# v1.net
KiCad netlist of a schematic drawn in EAGLE
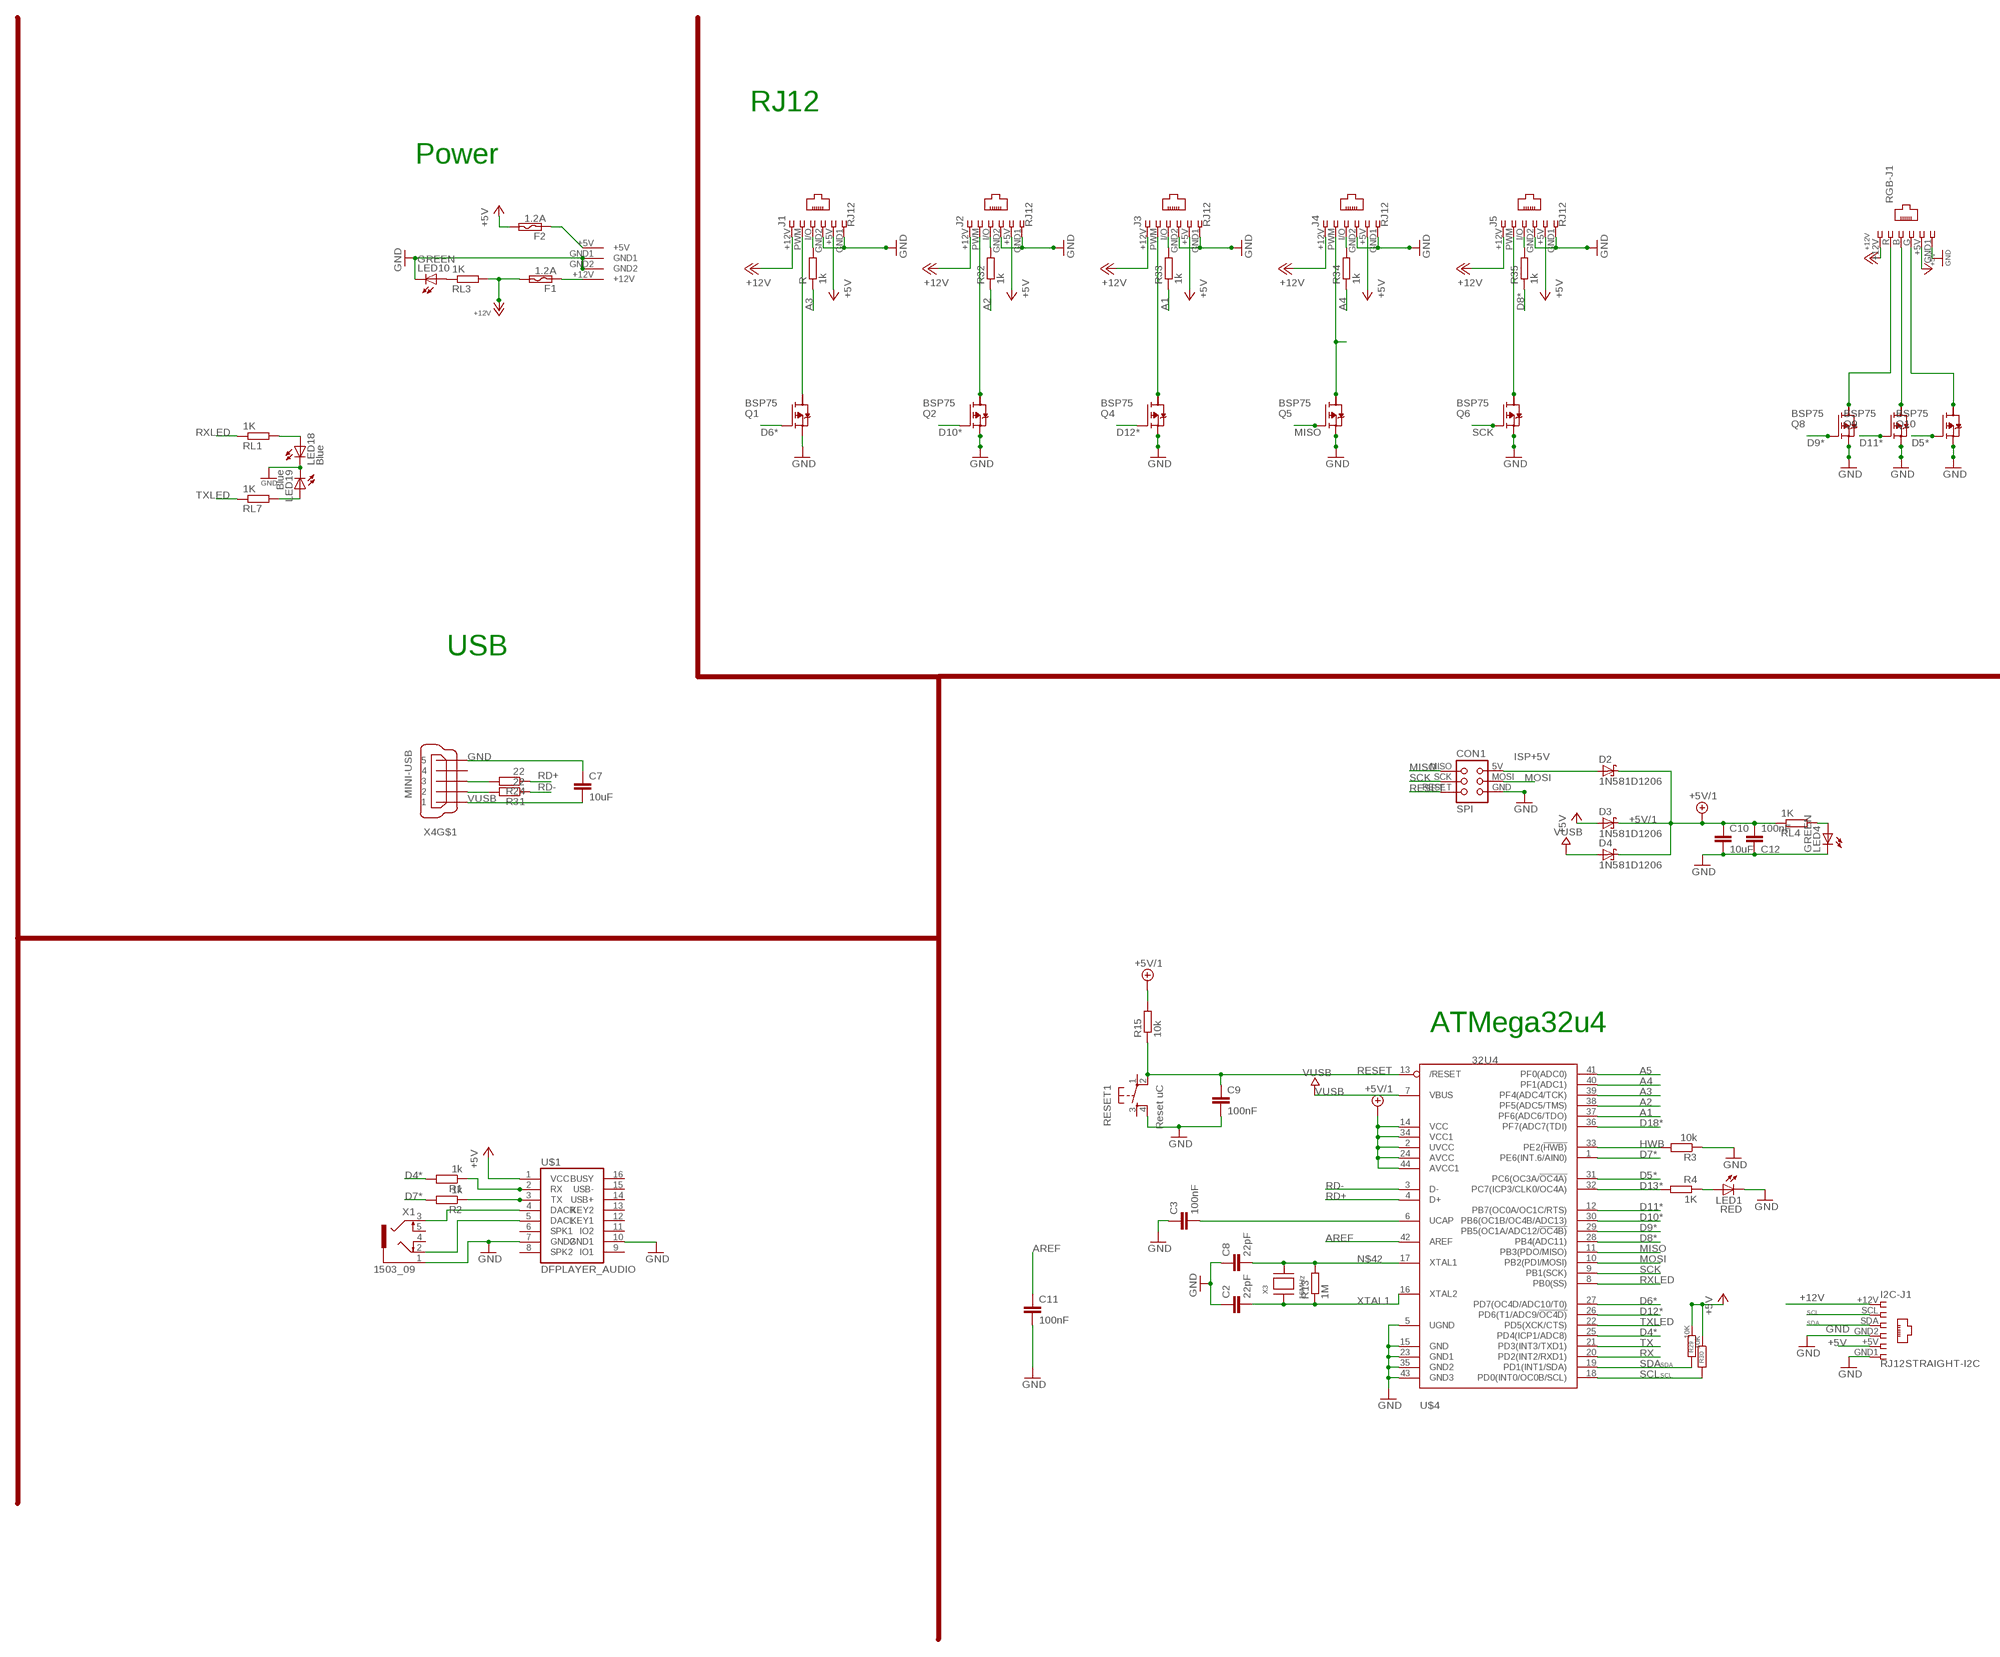
[diagram p0: schematic, sheet 1, part 1 of 2]
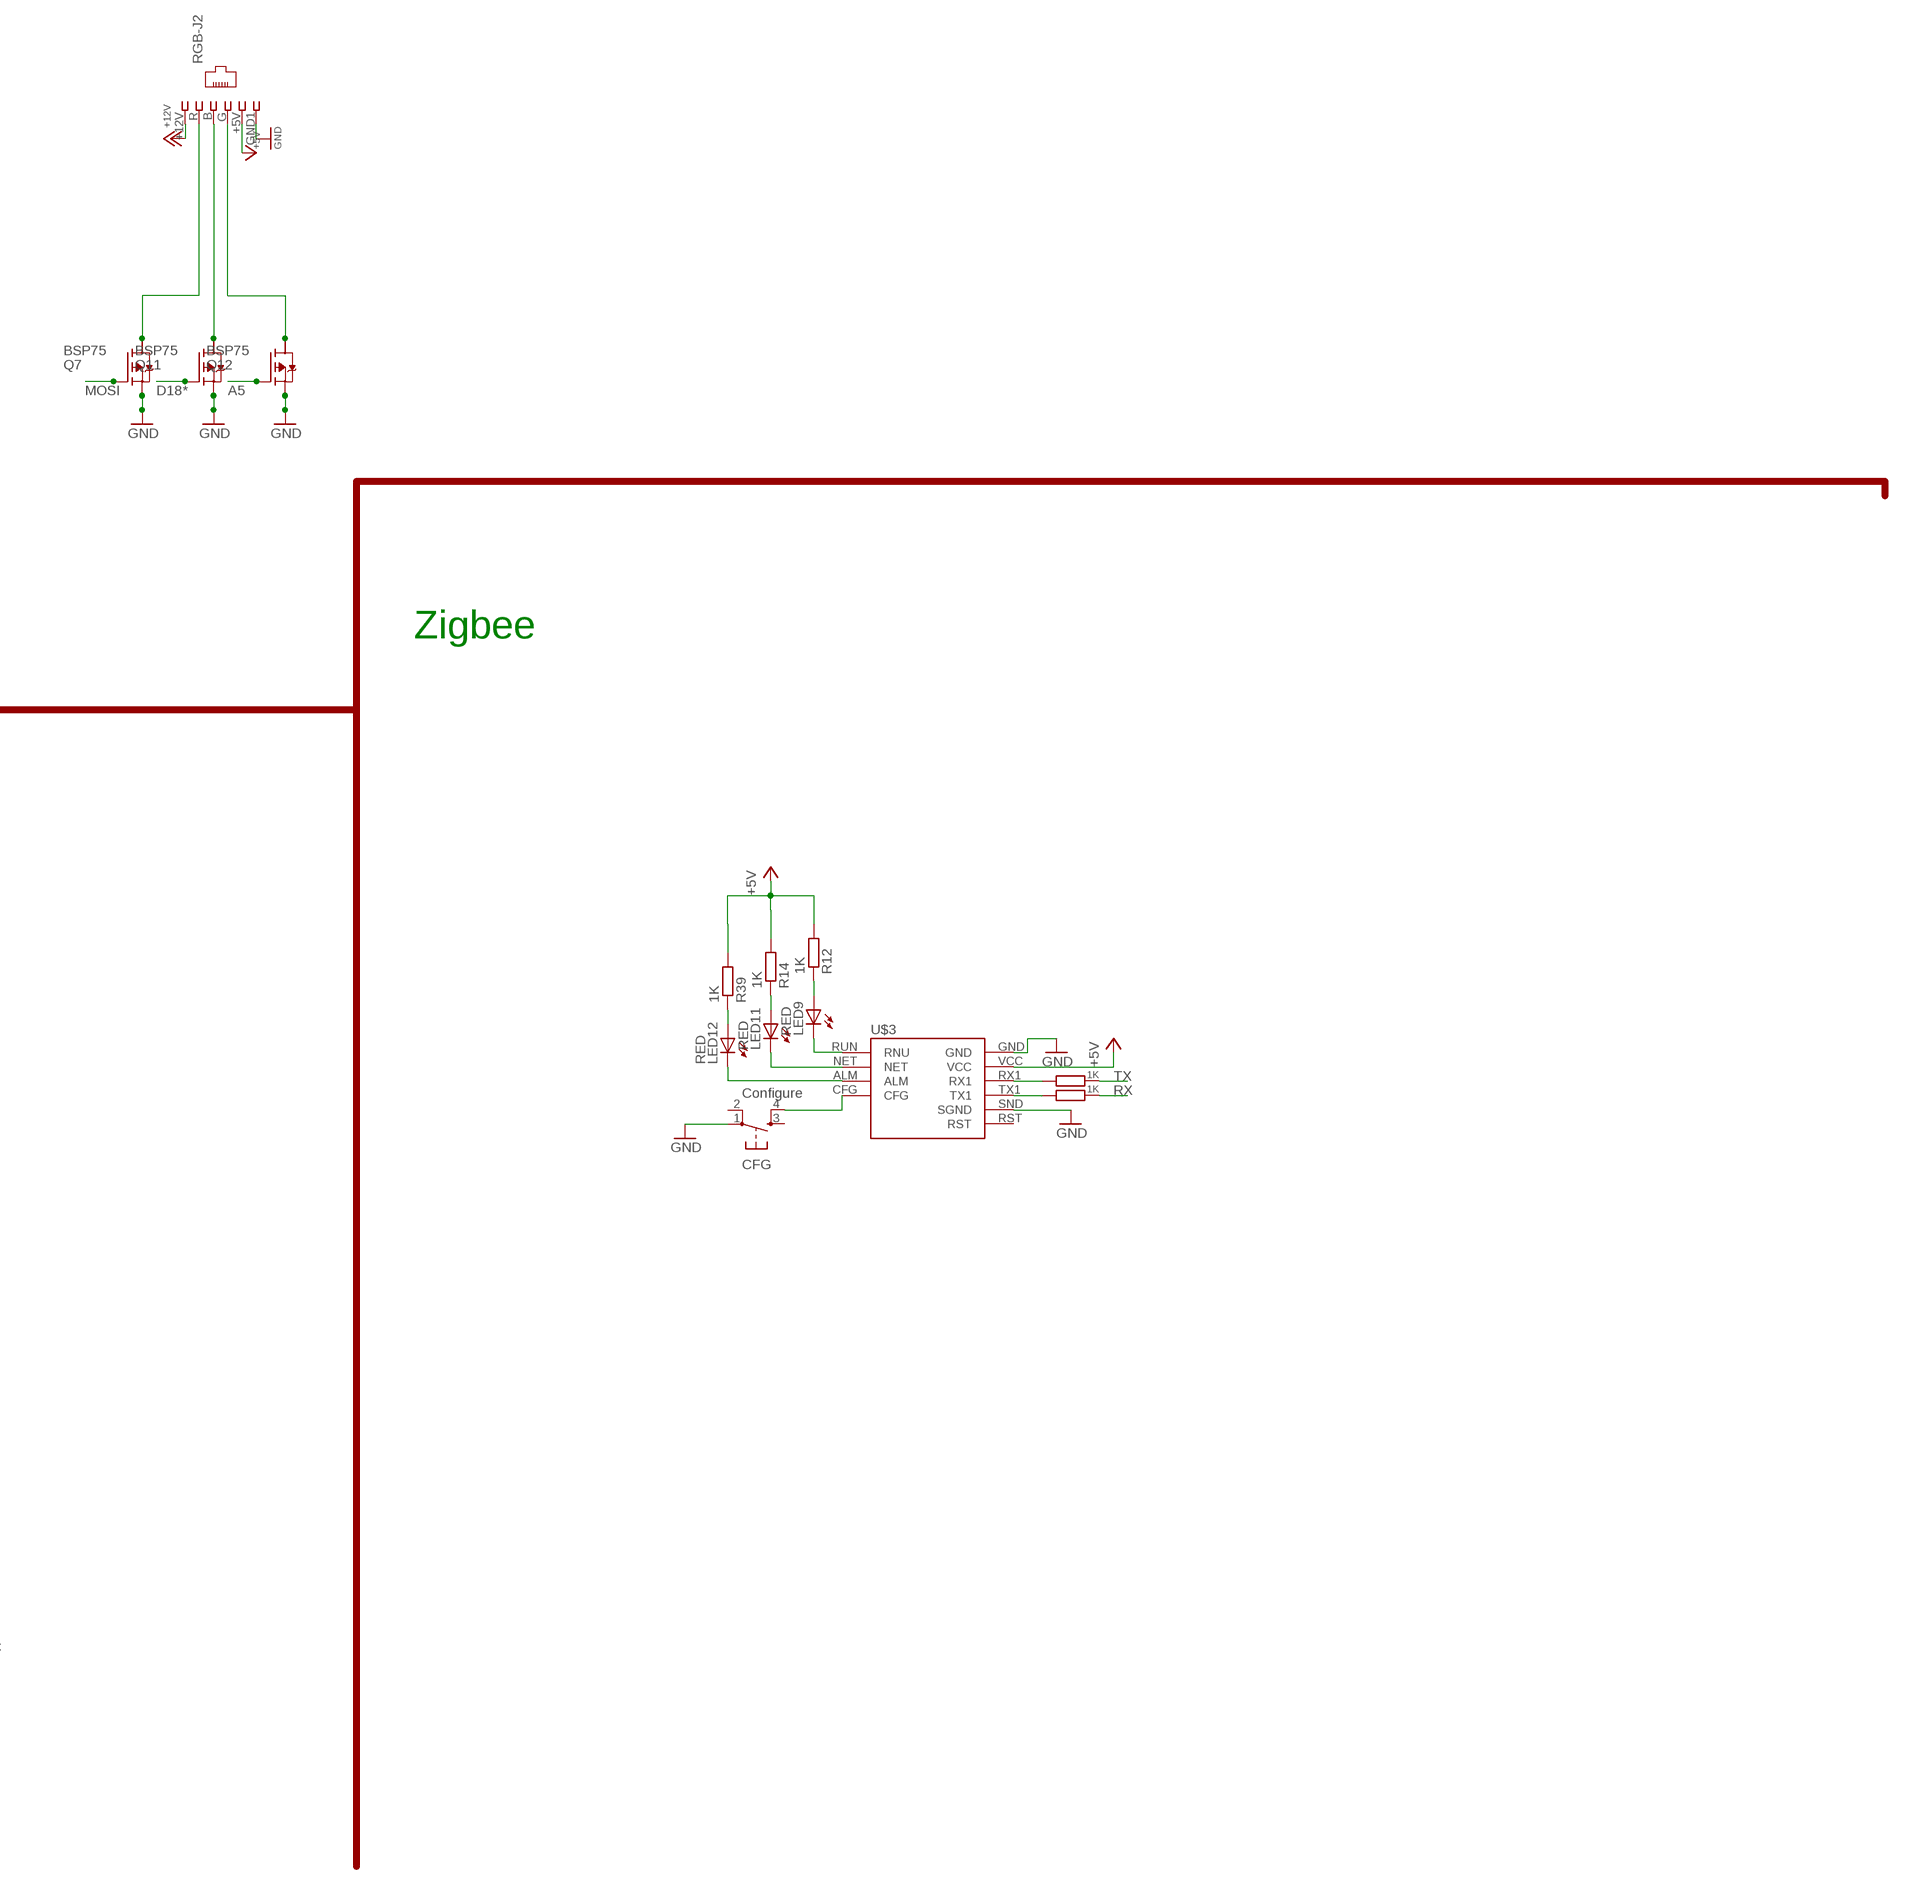
[diagram p1: schematic, sheet 1, part 2 of 2]

(export (version "E")
  (design (tool "Eeschema 10.0.6"))
  (components
    (comp (ref "C2")
      (value "22pF")
      (footprint "eagle-import:C1206")
      (libsource (lib "eagle-import") (part "C-EUC1206"))
    )
    (comp (ref "C3")
      (value "100nF")
      (footprint "eagle-import:C1206")
      (libsource (lib "eagle-import") (part "C-EUC1206"))
    )
    (comp (ref "C7")
      (value "10uF")
      (footprint "eagle-import:C1206")
      (libsource (lib "eagle-import") (part "C-EUC1206"))
    )
    (comp (ref "C8")
      (value "22pF")
      (footprint "eagle-import:C1206")
      (libsource (lib "eagle-import") (part "C-EUC1206"))
    )
    (comp (ref "C9")
      (value "100nF")
      (footprint "eagle-import:C1206")
      (libsource (lib "eagle-import") (part "C-EUC1206"))
    )
    (comp (ref "C10")
      (value "10uF")
      (footprint "eagle-import:C1206")
      (libsource (lib "eagle-import") (part "C-EUC1206"))
    )
    (comp (ref "C11")
      (value "100nF")
      (footprint "eagle-import:C1206")
      (libsource (lib "eagle-import") (part "C-EUC1206"))
    )
    (comp (ref "C12")
      (value "100nF")
      (footprint "eagle-import:C1206")
      (libsource (lib "eagle-import") (part "C-EUC1206"))
    )
    (comp (ref "CFG")
      (value "Configure")
      (footprint "eagle-import:TACTILE_SWITCH_SMD")
      (libsource (lib "eagle-import") (part "TAC_SWITCHSMD"))
    )
    (comp (ref "CON1")
      (value "SPI")
      (footprint "eagle-import:TC2030-MCP-NL")
      (libsource (lib "eagle-import") (part "TINYISPT"))
    )
    (comp (ref "D2")
      (value "1N581D1206")
      (footprint "eagle-import:LED-1206")
      (libsource (lib "eagle-import") (part "1N581D1206"))
    )
    (comp (ref "D3")
      (value "1N581D1206")
      (footprint "eagle-import:LED-1206")
      (libsource (lib "eagle-import") (part "1N581D1206"))
    )
    (comp (ref "D4")
      (value "1N581D1206")
      (footprint "eagle-import:LED-1206")
      (libsource (lib "eagle-import") (part "1N581D1206"))
    )
    (comp (ref "F1")
      (value "1.2A")
      (footprint "eagle-import:C1812")
      (libsource (lib "eagle-import") (part "POLYSWITCHSMD1812"))
    )
    (comp (ref "F2")
      (value "1.2A")
      (footprint "eagle-import:C1812")
      (libsource (lib "eagle-import") (part "POLYSWITCHSMD1812"))
    )
    (comp (ref "I2C-J1")
      (value "RJ12STRAIGHT-I2C")
      (footprint "eagle-import:RJ12-STRAIGHT-I2C")
      (libsource (lib "eagle-import") (part "RJ12STRAIGHT-I2C"))
    )
    (comp (ref "J1")
      (value "RJ12")
      (footprint "eagle-import:RJ12-STRAIGHT")
      (libsource (lib "eagle-import") (part "RJ12STRAIGHT"))
    )
    (comp (ref "J2")
      (value "RJ12")
      (footprint "eagle-import:RJ12-STRAIGHT")
      (libsource (lib "eagle-import") (part "RJ12STRAIGHT"))
    )
    (comp (ref "J3")
      (value "RJ12")
      (footprint "eagle-import:RJ12-STRAIGHT")
      (libsource (lib "eagle-import") (part "RJ12STRAIGHT"))
    )
    (comp (ref "J4")
      (value "RJ12")
      (footprint "eagle-import:RJ12-STRAIGHT")
      (libsource (lib "eagle-import") (part "RJ12STRAIGHT"))
    )
    (comp (ref "J5")
      (value "RJ12")
      (footprint "eagle-import:RJ12-STRAIGHT")
      (libsource (lib "eagle-import") (part "RJ12STRAIGHT"))
    )
    (comp (ref "LED1")
      (value "RED")
      (footprint "eagle-import:CHIP-LED0805")
      (libsource (lib "eagle-import") (part "LEDCHIP-LED0805"))
    )
    (comp (ref "LED4")
      (value "GREEN")
      (footprint "eagle-import:CHIP-LED0805")
      (libsource (lib "eagle-import") (part "LEDCHIP-LED0805"))
    )
    (comp (ref "LED9")
      (value "RED")
      (footprint "eagle-import:CHIP-LED0805")
      (libsource (lib "eagle-import") (part "LEDCHIP-LED0805"))
    )
    (comp (ref "LED10")
      (value "GREEN")
      (footprint "eagle-import:CHIP-LED0805")
      (libsource (lib "eagle-import") (part "LEDCHIP-LED0805"))
    )
    (comp (ref "LED11")
      (value "RED")
      (footprint "eagle-import:CHIP-LED0805")
      (libsource (lib "eagle-import") (part "LEDCHIP-LED0805"))
    )
    (comp (ref "LED12")
      (value "RED")
      (footprint "eagle-import:CHIP-LED0805")
      (libsource (lib "eagle-import") (part "LEDCHIP-LED0805"))
    )
    (comp (ref "LED18")
      (value "Blue")
      (footprint "eagle-import:CHIP-LED0805")
      (libsource (lib "eagle-import") (part "LEDCHIP-LED0805"))
    )
    (comp (ref "LED19")
      (value "Blue")
      (footprint "eagle-import:CHIP-LED0805")
      (libsource (lib "eagle-import") (part "LEDCHIP-LED0805"))
    )
    (comp (ref "Q1")
      (value "BSP75")
      (footprint "eagle-import:PG-SOT-223")
      (libsource (lib "eagle-import") (part "BSP613P"))
    )
    (comp (ref "Q2")
      (value "BSP75")
      (footprint "eagle-import:PG-SOT-223")
      (libsource (lib "eagle-import") (part "BSP613P"))
    )
    (comp (ref "Q4")
      (value "BSP75")
      (footprint "eagle-import:PG-SOT-223")
      (libsource (lib "eagle-import") (part "BSP613P"))
    )
    (comp (ref "Q5")
      (value "BSP75")
      (footprint "eagle-import:PG-SOT-223")
      (libsource (lib "eagle-import") (part "BSP613P"))
    )
    (comp (ref "Q6")
      (value "BSP75")
      (footprint "eagle-import:PG-SOT-223")
      (libsource (lib "eagle-import") (part "BSP613P"))
    )
    (comp (ref "Q7")
      (value "BSP75")
      (footprint "eagle-import:PG-SOT-223")
      (libsource (lib "eagle-import") (part "BSP613P"))
    )
    (comp (ref "Q8")
      (value "BSP75")
      (footprint "eagle-import:PG-SOT-223")
      (libsource (lib "eagle-import") (part "BSP613P"))
    )
    (comp (ref "Q9")
      (value "BSP75")
      (footprint "eagle-import:PG-SOT-223")
      (libsource (lib "eagle-import") (part "BSP613P"))
    )
    (comp (ref "Q10")
      (value "BSP75")
      (footprint "eagle-import:PG-SOT-223")
      (libsource (lib "eagle-import") (part "BSP613P"))
    )
    (comp (ref "Q11")
      (value "BSP75")
      (footprint "eagle-import:PG-SOT-223")
      (libsource (lib "eagle-import") (part "BSP613P"))
    )
    (comp (ref "Q12")
      (value "BSP75")
      (footprint "eagle-import:PG-SOT-223")
      (libsource (lib "eagle-import") (part "BSP613P"))
    )
    (comp (ref "R")
      (value "1k")
      (footprint "eagle-import:R0805")
      (libsource (lib "eagle-import") (part "R-EU_R0805"))
    )
    (comp (ref "R1")
      (value "1k")
      (footprint "eagle-import:R0805")
      (libsource (lib "eagle-import") (part "R-EU_R0805"))
    )
    (comp (ref "R2")
      (value "1k")
      (footprint "eagle-import:R0805")
      (libsource (lib "eagle-import") (part "R-EU_R0805"))
    )
    (comp (ref "R3")
      (value "10k")
      (footprint "eagle-import:M0805")
      (libsource (lib "eagle-import") (part "resistor_R-EU_M0805"))
    )
    (comp (ref "R4")
      (value "1K")
      (footprint "eagle-import:R0805")
      (libsource (lib "eagle-import") (part "R-EU_R0805"))
    )
    (comp (ref "R8")
      (value "1K")
      (footprint "eagle-import:R0805")
      (libsource (lib "eagle-import") (part "R-EU_R0805"))
    )
    (comp (ref "R11")
      (value "1K")
      (footprint "eagle-import:R0805")
      (libsource (lib "eagle-import") (part "R-EU_R0805"))
    )
    (comp (ref "R12")
      (value "1K")
      (footprint "eagle-import:R0805")
      (libsource (lib "eagle-import") (part "R-EU_R0805"))
    )
    (comp (ref "R13")
      (value "1M")
      (footprint "eagle-import:R1206")
      (libsource (lib "eagle-import") (part "R-EU_R1206"))
    )
    (comp (ref "R14")
      (value "1K")
      (footprint "eagle-import:R0805")
      (libsource (lib "eagle-import") (part "R-EU_R0805"))
    )
    (comp (ref "R15")
      (value "10k")
      (footprint "eagle-import:M0805")
      (libsource (lib "eagle-import") (part "resistor_R-EU_M0805"))
    )
    (comp (ref "R24")
      (value "22")
      (footprint "eagle-import:M1206")
      (libsource (lib "eagle-import") (part "resistor_R-EU_M1206"))
    )
    (comp (ref "R29")
      (value "10K")
      (footprint "eagle-import:M0805")
      (libsource (lib "eagle-import") (part "resistor_R-EU_M0805"))
    )
    (comp (ref "R30")
      (value "10K")
      (footprint "eagle-import:M0805")
      (libsource (lib "eagle-import") (part "resistor_R-EU_M0805"))
    )
    (comp (ref "R31")
      (value "22")
      (footprint "eagle-import:M1206")
      (libsource (lib "eagle-import") (part "resistor_R-EU_M1206"))
    )
    (comp (ref "R32")
      (value "1k")
      (footprint "eagle-import:R0805")
      (libsource (lib "eagle-import") (part "R-EU_R0805"))
    )
    (comp (ref "R33")
      (value "1k")
      (footprint "eagle-import:R0805")
      (libsource (lib "eagle-import") (part "R-EU_R0805"))
    )
    (comp (ref "R34")
      (value "1k")
      (footprint "eagle-import:R0805")
      (libsource (lib "eagle-import") (part "R-EU_R0805"))
    )
    (comp (ref "R35")
      (value "1k")
      (footprint "eagle-import:R0805")
      (libsource (lib "eagle-import") (part "R-EU_R0805"))
    )
    (comp (ref "R39")
      (value "1K")
      (footprint "eagle-import:R0805")
      (libsource (lib "eagle-import") (part "R-EU_R0805"))
    )
    (comp (ref "RESET1")
      (value "Reset uC")
      (footprint "eagle-import:TACTILE_SWITCH_SMD")
      (libsource (lib "eagle-import") (part "TAC_SWITCHSMD"))
    )
    (comp (ref "RGB-J1")
      (value "RJ12")
      (footprint "eagle-import:RJ12-STRAIGHT-RGB")
      (libsource (lib "eagle-import") (part "RJ12STRAIGHT-RGB"))
    )
    (comp (ref "RGB-J2")
      (value "RJ12")
      (footprint "eagle-import:RJ12-STRAIGHT-RGB")
      (libsource (lib "eagle-import") (part "RJ12STRAIGHT-RGB"))
    )
    (comp (ref "RL1")
      (value "1K")
      (footprint "eagle-import:R0805")
      (libsource (lib "eagle-import") (part "R-EU_R0805"))
    )
    (comp (ref "RL3")
      (value "1K")
      (footprint "eagle-import:R0805")
      (libsource (lib "eagle-import") (part "R-EU_R0805"))
    )
    (comp (ref "RL4")
      (value "1K")
      (footprint "eagle-import:R0805")
      (libsource (lib "eagle-import") (part "resistor_R-EU_R0805"))
    )
    (comp (ref "RL7")
      (value "1K")
      (footprint "eagle-import:R0805")
      (libsource (lib "eagle-import") (part "R-EU_R0805"))
    )
    (comp (ref "U$1")
      (value "DFPLAYER_AUDIO")
      (footprint "eagle-import:DIL16-7")
      (libsource (lib "eagle-import") (part "DFPLAYER_AUDIO"))
    )
    (comp (ref "U$3")
      (value "SZ05-ZIGBEESMD")
      (footprint "eagle-import:SZ05-ZIGBEE3")
      (libsource (lib "eagle-import") (part "SZ05-ZIGBEESMD"))
    )
    (comp (ref "U$4")
      (value "32U4")
      (footprint "eagle-import:TQFP44")
      (libsource (lib "eagle-import") (part "ATMEGA32U4-AU"))
    )
    (comp (ref "U$6")
      (value "KPJX-4S-S")
      (footprint "eagle-import:KPJX-4S-S")
      (libsource (lib "eagle-import") (part "KPJX-4S-S"))
    )
    (comp (ref "X1")
      (value "1503_09")
      (footprint "eagle-import:1503_09")
      (libsource (lib "eagle-import") (part "1503_09"))
    )
    (comp (ref "X3")
      (value "16MHz")
      (footprint "eagle-import:NX6035")
      (libsource (lib "eagle-import") (part "XTALNX6035"))
    )
    (comp (ref "X4")
      (value "MINI-USB")
      (footprint "eagle-import:32005-201")
      (libsource (lib "eagle-import") (part "MINI-USB-SCHIELD-32005-201"))
    )
  )
  (nets
    (net (code "1") (name "+5V") (class "Default")
      (node (ref "D3") (pin "A") (pinfunction "A_A") (pintype "passive"))
      (node (ref "F2") (pin "2") (pinfunction "2_2") (pintype "passive"))
      (node (ref "I2C-J1") (pin "+5V") (pinfunction "5_+5V") (pintype "bidirectional"))
      (node (ref "J1") (pin "+5V") (pinfunction "5_+5V") (pintype "bidirectional"))
      (node (ref "J2") (pin "+5V") (pinfunction "5_+5V") (pintype "bidirectional"))
      (node (ref "J3") (pin "+5V") (pinfunction "5_+5V") (pintype "bidirectional"))
      (node (ref "J4") (pin "+5V") (pinfunction "5_+5V") (pintype "bidirectional"))
      (node (ref "J5") (pin "+5V") (pinfunction "5_+5V") (pintype "bidirectional"))
      (node (ref "R12") (pin "2") (pinfunction "2_2") (pintype "passive"))
      (node (ref "R14") (pin "2") (pinfunction "2_2") (pintype "passive"))
      (node (ref "R29") (pin "1") (pinfunction "1_1") (pintype "passive"))
      (node (ref "R30") (pin "1") (pinfunction "1_1") (pintype "passive"))
      (node (ref "R39") (pin "2") (pinfunction "2_2") (pintype "passive"))
      (node (ref "RGB-J1") (pin "+5V") (pinfunction "5_+5V") (pintype "bidirectional"))
      (node (ref "RGB-J2") (pin "+5V") (pinfunction "5_+5V") (pintype "bidirectional"))
      (node (ref "U$1") (pin "1") (pinfunction "VCC_1") (pintype "power_in"))
      (node (ref "U$3") (pin "VCC") (pinfunction "VCC_VCC") (pintype "bidirectional"))
    )
    (net (code "2") (name "+5V{slash}1") (class "Default")
      (node (ref "C10") (pin "1") (pinfunction "1_1") (pintype "passive"))
      (node (ref "C12") (pin "2") (pinfunction "2_2") (pintype "passive"))
      (node (ref "D2") (pin "C") (pinfunction "C_C") (pintype "passive"))
      (node (ref "D3") (pin "C") (pinfunction "C_C") (pintype "passive"))
      (node (ref "D4") (pin "C") (pinfunction "C_C") (pintype "passive"))
      (node (ref "R15") (pin "2") (pinfunction "2_2") (pintype "passive"))
      (node (ref "RL4") (pin "1") (pinfunction "1_1") (pintype "passive"))
      (node (ref "U$4") (pin "14") (pinfunction "VCC_14") (pintype "bidirectional"))
      (node (ref "U$4") (pin "2") (pinfunction "UVCC_2") (pintype "bidirectional"))
      (node (ref "U$4") (pin "24") (pinfunction "AVCC_24") (pintype "bidirectional"))
      (node (ref "U$4") (pin "34") (pinfunction "VCC1_34") (pintype "bidirectional"))
      (node (ref "U$4") (pin "44") (pinfunction "AVCC1_44") (pintype "bidirectional"))
    )
    (net (code "3") (name "+12V") (class "Default")
      (node (ref "F1") (pin "2") (pinfunction "2_2") (pintype "passive"))
      (node (ref "I2C-J1") (pin "+12V") (pinfunction "1_+12V") (pintype "bidirectional"))
      (node (ref "J1") (pin "+12V") (pinfunction "1_+12V") (pintype "bidirectional"))
      (node (ref "J2") (pin "+12V") (pinfunction "1_+12V") (pintype "bidirectional"))
      (node (ref "J3") (pin "+12V") (pinfunction "1_+12V") (pintype "bidirectional"))
      (node (ref "J4") (pin "+12V") (pinfunction "1_+12V") (pintype "bidirectional"))
      (node (ref "J5") (pin "+12V") (pinfunction "1_+12V") (pintype "bidirectional"))
      (node (ref "RGB-J1") (pin "+12V") (pinfunction "1_+12V") (pintype "bidirectional"))
      (node (ref "RGB-J2") (pin "+12V") (pinfunction "1_+12V") (pintype "bidirectional"))
      (node (ref "RL3") (pin "2") (pinfunction "2_2") (pintype "passive"))
    )
    (net (code "4") (name "/A1") (class "Default")
      (node (ref "R33") (pin "1") (pinfunction "1_1") (pintype "passive"))
      (node (ref "U$4") (pin "37") (pinfunction "PF6(ADC6/TDO)_37") (pintype "bidirectional"))
    )
    (net (code "5") (name "/A2") (class "Default")
      (node (ref "R32") (pin "1") (pinfunction "1_1") (pintype "passive"))
      (node (ref "U$4") (pin "38") (pinfunction "PF5(ADC5/TMS)_38") (pintype "bidirectional"))
    )
    (net (code "6") (name "/A3") (class "Default")
      (node (ref "R") (pin "1") (pinfunction "1_1") (pintype "passive"))
      (node (ref "U$4") (pin "39") (pinfunction "PF4(ADC4/TCK)_39") (pintype "bidirectional"))
    )
    (net (code "7") (name "/A4") (class "Default")
      (node (ref "R34") (pin "1") (pinfunction "1_1") (pintype "passive"))
      (node (ref "U$4") (pin "40") (pinfunction "PF1(ADC1)_40") (pintype "bidirectional"))
    )
    (net (code "8") (name "/A5") (class "Default")
      (node (ref "Q12") (pin "1") (pinfunction "G_1") (pintype "passive"))
      (node (ref "U$4") (pin "41") (pinfunction "PF0(ADC0)_41") (pintype "bidirectional"))
    )
    (net (code "9") (name "/AREF") (class "Default")
      (node (ref "C11") (pin "1") (pinfunction "1_1") (pintype "passive"))
      (node (ref "U$4") (pin "42") (pinfunction "AREF_42") (pintype "bidirectional"))
    )
    (net (code "10") (name "/D4*") (class "Default")
      (node (ref "R1") (pin "2") (pinfunction "2_2") (pintype "passive"))
      (node (ref "U$4") (pin "25") (pinfunction "PD4(ICP1/ADC8)_25") (pintype "bidirectional"))
    )
    (net (code "11") (name "/D5*") (class "Default")
      (node (ref "Q10") (pin "1") (pinfunction "G_1") (pintype "passive"))
      (node (ref "U$4") (pin "31") (pinfunction "PC6(OC3A/~{OC4A})_31") (pintype "bidirectional"))
    )
    (net (code "12") (name "/D6*") (class "Default")
      (node (ref "Q1") (pin "1") (pinfunction "G_1") (pintype "passive"))
      (node (ref "U$4") (pin "27") (pinfunction "PD7(OC4D/ADC10/T0)_27") (pintype "bidirectional"))
    )
    (net (code "13") (name "/D7*") (class "Default")
      (node (ref "R2") (pin "2") (pinfunction "2_2") (pintype "passive"))
      (node (ref "U$4") (pin "1") (pinfunction "PE6(INT.6/AIN0)_1") (pintype "bidirectional"))
    )
    (net (code "14") (name "/D8*") (class "Default")
      (node (ref "R35") (pin "1") (pinfunction "1_1") (pintype "passive"))
      (node (ref "U$4") (pin "28") (pinfunction "PB4(ADC11)_28") (pintype "bidirectional"))
    )
    (net (code "15") (name "/D9*") (class "Default")
      (node (ref "Q8") (pin "1") (pinfunction "G_1") (pintype "passive"))
      (node (ref "U$4") (pin "29") (pinfunction "PB5(OC1A/ADC12/~{OC4B})_29") (pintype "bidirectional"))
    )
    (net (code "16") (name "/D10*") (class "Default")
      (node (ref "Q2") (pin "1") (pinfunction "G_1") (pintype "passive"))
      (node (ref "U$4") (pin "30") (pinfunction "PB6(OC1B/OC4B/ADC13)_30") (pintype "bidirectional"))
    )
    (net (code "17") (name "/D11*") (class "Default")
      (node (ref "Q9") (pin "1") (pinfunction "G_1") (pintype "passive"))
      (node (ref "U$4") (pin "12") (pinfunction "PB7(OC0A/OC1C/RTS)_12") (pintype "bidirectional"))
    )
    (net (code "18") (name "/D12*") (class "Default")
      (node (ref "Q4") (pin "1") (pinfunction "G_1") (pintype "passive"))
      (node (ref "U$4") (pin "26") (pinfunction "PD6(T1/ADC9/~{OC4D})_26") (pintype "bidirectional"))
    )
    (net (code "19") (name "/D13*") (class "Default")
      (node (ref "R4") (pin "2") (pinfunction "2_2") (pintype "passive"))
      (node (ref "U$4") (pin "32") (pinfunction "PC7(ICP3/CLK0/OC4A)_32") (pintype "bidirectional"))
    )
    (net (code "20") (name "/D18*") (class "Default")
      (node (ref "Q11") (pin "1") (pinfunction "G_1") (pintype "passive"))
      (node (ref "U$4") (pin "36") (pinfunction "PF7(ADC7(TDI)_36") (pintype "bidirectional"))
    )
    (net (code "21") (name "/HWB") (class "Default")
      (node (ref "R3") (pin "2") (pinfunction "2_2") (pintype "passive"))
      (node (ref "U$4") (pin "33") (pinfunction "PE2(~{HWB})_33") (pintype "bidirectional"))
    )
    (net (code "22") (name "/ISP+5V") (class "Default")
      (node (ref "CON1") (pin "5V") (pinfunction "VCC_5V") (pintype "passive"))
      (node (ref "D2") (pin "A") (pinfunction "A_A") (pintype "passive"))
    )
    (net (code "23") (name "/MISO") (class "Default")
      (node (ref "CON1") (pin "MISO") (pinfunction "MISO_MISO") (pintype "passive"))
      (node (ref "Q5") (pin "1") (pinfunction "G_1") (pintype "passive"))
      (node (ref "U$4") (pin "11") (pinfunction "PB3(PDO/MISO)_11") (pintype "bidirectional"))
    )
    (net (code "24") (name "/MOSI") (class "Default")
      (node (ref "CON1") (pin "MOSI") (pinfunction "MOSI_MOSI") (pintype "passive"))
      (node (ref "Q7") (pin "1") (pinfunction "G_1") (pintype "passive"))
      (node (ref "U$4") (pin "10") (pinfunction "PB2(PDI/MOSI)_10") (pintype "bidirectional"))
    )
    (net (code "25") (name "/N$42") (class "Default")
      (node (ref "C8") (pin "2") (pinfunction "2_2") (pintype "passive"))
      (node (ref "R13") (pin "2") (pinfunction "2_2") (pintype "passive"))
      (node (ref "U$4") (pin "17") (pinfunction "XTAL1_17") (pintype "bidirectional"))
      (node (ref "X3") (pin "P$2") (pinfunction "P$2_P$2") (pintype "bidirectional"))
    )
    (net (code "26") (name "/RD+") (class "Default")
      (node (ref "R24") (pin "1") (pinfunction "1_1") (pintype "passive"))
      (node (ref "U$4") (pin "4") (pinfunction "D+_4") (pintype "bidirectional"))
    )
    (net (code "27") (name "/RD-") (class "Default")
      (node (ref "R31") (pin "1") (pinfunction "1_1") (pintype "passive"))
      (node (ref "U$4") (pin "3") (pinfunction "D-_3") (pintype "bidirectional"))
    )
    (net (code "28") (name "/RESET") (class "Default")
      (node (ref "C9") (pin "1") (pinfunction "1_1") (pintype "passive"))
      (node (ref "CON1") (pin "RESET") (pinfunction "RESET_RESET") (pintype "passive"))
      (node (ref "R15") (pin "1") (pinfunction "1_1") (pintype "passive"))
      (node (ref "RESET1") (pin "2") (pinfunction "2_2") (pintype "passive"))
      (node (ref "U$4") (pin "13") (pinfunction "/RESET_13") (pintype "bidirectional"))
    )
    (net (code "29") (name "/RX") (class "Default")
      (node (ref "R8") (pin "1") (pinfunction "1_1") (pintype "passive"))
      (node (ref "U$4") (pin "20") (pinfunction "PD2(INT2/RXD1)_20") (pintype "bidirectional"))
    )
    (net (code "30") (name "/RXLED") (class "Default")
      (node (ref "RL1") (pin "1") (pinfunction "1_1") (pintype "passive"))
      (node (ref "U$4") (pin "8") (pinfunction "PB0(SS)_8") (pintype "bidirectional"))
    )
    (net (code "31") (name "/SCK") (class "Default")
      (node (ref "CON1") (pin "SCK") (pinfunction "SCK_SCK") (pintype "passive"))
      (node (ref "Q6") (pin "1") (pinfunction "G_1") (pintype "passive"))
      (node (ref "U$4") (pin "9") (pinfunction "PB1(SCK)_9") (pintype "bidirectional"))
    )
    (net (code "32") (name "/SCL") (class "Default")
      (node (ref "I2C-J1") (pin "SCL") (pinfunction "2_SCL") (pintype "bidirectional"))
      (node (ref "R30") (pin "2") (pinfunction "2_2") (pintype "passive"))
      (node (ref "U$4") (pin "18") (pinfunction "PD0(INT0/OC0B/SCL)_18") (pintype "bidirectional"))
    )
    (net (code "33") (name "/SDA") (class "Default")
      (node (ref "I2C-J1") (pin "SDA") (pinfunction "3_SDA") (pintype "bidirectional"))
      (node (ref "R29") (pin "2") (pinfunction "2_2") (pintype "passive"))
      (node (ref "U$4") (pin "19") (pinfunction "PD1(INT1/SDA)_19") (pintype "bidirectional"))
    )
    (net (code "34") (name "/TX") (class "Default")
      (node (ref "R11") (pin "1") (pinfunction "1_1") (pintype "passive"))
      (node (ref "U$4") (pin "21") (pinfunction "PD3(INT3/TXD1)_21") (pintype "bidirectional"))
    )
    (net (code "35") (name "/TXLED") (class "Default")
      (node (ref "RL7") (pin "1") (pinfunction "1_1") (pintype "passive"))
      (node (ref "U$4") (pin "22") (pinfunction "PD5(XCK/CTS)_22") (pintype "bidirectional"))
    )
    (net (code "36") (name "/XTAL1") (class "Default")
      (node (ref "C2") (pin "2") (pinfunction "2_2") (pintype "passive"))
      (node (ref "R13") (pin "1") (pinfunction "1_1") (pintype "passive"))
      (node (ref "U$4") (pin "16") (pinfunction "XTAL2_16") (pintype "bidirectional"))
      (node (ref "X3") (pin "P$1") (pinfunction "P$1_P$1") (pintype "bidirectional"))
    )
    (net (code "37") (name "GND") (class "Default")
      (node (ref "C10") (pin "2") (pinfunction "2_2") (pintype "passive"))
      (node (ref "C11") (pin "2") (pinfunction "2_2") (pintype "passive"))
      (node (ref "C12") (pin "1") (pinfunction "1_1") (pintype "passive"))
      (node (ref "C2") (pin "1") (pinfunction "1_1") (pintype "passive"))
      (node (ref "C3") (pin "1") (pinfunction "1_1") (pintype "passive"))
      (node (ref "C7") (pin "1") (pinfunction "1_1") (pintype "passive"))
      (node (ref "C8") (pin "1") (pinfunction "1_1") (pintype "passive"))
      (node (ref "C9") (pin "2") (pinfunction "2_2") (pintype "passive"))
      (node (ref "CFG") (pin "1") (pinfunction "1_1") (pintype "passive"))
      (node (ref "CON1") (pin "GND") (pinfunction "GND_GND") (pintype "passive"))
      (node (ref "I2C-J1") (pin "GND1") (pinfunction "6_GND1") (pintype "bidirectional"))
      (node (ref "I2C-J1") (pin "GND2") (pinfunction "4_GND2") (pintype "bidirectional"))
      (node (ref "J1") (pin "GND1") (pinfunction "6_GND1") (pintype "bidirectional"))
      (node (ref "J1") (pin "GND2") (pinfunction "4_GND2") (pintype "bidirectional"))
      (node (ref "J2") (pin "GND1") (pinfunction "6_GND1") (pintype "bidirectional"))
      (node (ref "J2") (pin "GND2") (pinfunction "4_GND2") (pintype "bidirectional"))
      (node (ref "J3") (pin "GND1") (pinfunction "6_GND1") (pintype "bidirectional"))
      (node (ref "J3") (pin "GND2") (pinfunction "4_GND2") (pintype "bidirectional"))
      (node (ref "J4") (pin "GND1") (pinfunction "6_GND1") (pintype "bidirectional"))
      (node (ref "J4") (pin "GND2") (pinfunction "4_GND2") (pintype "bidirectional"))
      (node (ref "J5") (pin "GND1") (pinfunction "6_GND1") (pintype "bidirectional"))
      (node (ref "J5") (pin "GND2") (pinfunction "4_GND2") (pintype "bidirectional"))
      (node (ref "LED1") (pin "C") (pinfunction "C_C") (pintype "passive"))
      (node (ref "LED10") (pin "C") (pinfunction "C_C") (pintype "passive"))
      (node (ref "LED18") (pin "C") (pinfunction "C_C") (pintype "passive"))
      (node (ref "LED19") (pin "C") (pinfunction "C_C") (pintype "passive"))
      (node (ref "LED4") (pin "C") (pinfunction "C_C") (pintype "passive"))
      (node (ref "Q1") (pin "3") (pinfunction "S_3") (pintype "passive"))
      (node (ref "Q10") (pin "3") (pinfunction "S_3") (pintype "passive"))
      (node (ref "Q11") (pin "3") (pinfunction "S_3") (pintype "passive"))
      (node (ref "Q12") (pin "3") (pinfunction "S_3") (pintype "passive"))
      (node (ref "Q2") (pin "3") (pinfunction "S_3") (pintype "passive"))
      (node (ref "Q4") (pin "3") (pinfunction "S_3") (pintype "passive"))
      (node (ref "Q5") (pin "3") (pinfunction "S_3") (pintype "passive"))
      (node (ref "Q6") (pin "3") (pinfunction "S_3") (pintype "passive"))
      (node (ref "Q7") (pin "3") (pinfunction "S_3") (pintype "passive"))
      (node (ref "Q8") (pin "3") (pinfunction "S_3") (pintype "passive"))
      (node (ref "Q9") (pin "3") (pinfunction "S_3") (pintype "passive"))
      (node (ref "R3") (pin "1") (pinfunction "1_1") (pintype "passive"))
      (node (ref "RESET1") (pin "4") (pinfunction "4_4") (pintype "passive"))
      (node (ref "RGB-J1") (pin "GND1") (pinfunction "6_GND1") (pintype "bidirectional"))
      (node (ref "RGB-J2") (pin "GND1") (pinfunction "6_GND1") (pintype "bidirectional"))
      (node (ref "U$1") (pin "10") (pinfunction "GND1_10") (pintype "power_in"))
      (node (ref "U$1") (pin "7") (pinfunction "GND2_7") (pintype "power_in"))
      (node (ref "U$3") (pin "GND") (pinfunction "GND_GND") (pintype "bidirectional"))
      (node (ref "U$3") (pin "SND") (pinfunction "SGND_SND") (pintype "bidirectional"))
      (node (ref "U$4") (pin "15") (pinfunction "GND_15") (pintype "bidirectional"))
      (node (ref "U$4") (pin "23") (pinfunction "GND1_23") (pintype "bidirectional"))
      (node (ref "U$4") (pin "35") (pinfunction "GND2_35") (pintype "bidirectional"))
      (node (ref "U$4") (pin "43") (pinfunction "GND3_43") (pintype "bidirectional"))
      (node (ref "U$4") (pin "5") (pinfunction "UGND_5") (pintype "bidirectional"))
      (node (ref "U$6") (pin "GND1") (pinfunction "GND1_GND1") (pintype "input"))
      (node (ref "U$6") (pin "GND2") (pinfunction "GND2_GND2") (pintype "input"))
      (node (ref "X1") (pin "1") (pinfunction "1_1") (pintype "passive"))
      (node (ref "X4") (pin "5") (pinfunction "5_5") (pintype "passive"))
    )
    (net (code "38") (name "Net-(CFG-Pad4)") (class "Default")
      (node (ref "CFG") (pin "4") (pinfunction "4_4") (pintype "passive"))
      (node (ref "U$3") (pin "CFG") (pinfunction "CFG_CFG") (pintype "bidirectional"))
    )
    (net (code "39") (name "Net-(F1-Pad1)") (class "Default")
      (node (ref "F1") (pin "1") (pinfunction "1_1") (pintype "passive"))
      (node (ref "U$6") (pin "+12V") (pinfunction "+12V_+12V") (pintype "power_in"))
    )
    (net (code "40") (name "Net-(F2-Pad1)") (class "Default")
      (node (ref "F2") (pin "1") (pinfunction "1_1") (pintype "passive"))
      (node (ref "U$6") (pin "+5V") (pinfunction "+5V_+5V") (pintype "power_in"))
    )
    (net (code "41") (name "Net-(J1-2)") (class "Default")
      (node (ref "J1") (pin "PWM") (pinfunction "2_PWM") (pintype "bidirectional"))
      (node (ref "Q1") (pin "2") (pinfunction "D_2") (pintype "passive"))
    )
    (net (code "42") (name "Net-(J1-3)") (class "Default")
      (node (ref "J1") (pin "I/O") (pinfunction "3_I/O") (pintype "bidirectional"))
      (node (ref "R") (pin "2") (pinfunction "2_2") (pintype "passive"))
    )
    (net (code "43") (name "Net-(J2-2)") (class "Default")
      (node (ref "J2") (pin "PWM") (pinfunction "2_PWM") (pintype "bidirectional"))
      (node (ref "Q2") (pin "2") (pinfunction "D_2") (pintype "passive"))
    )
    (net (code "44") (name "Net-(J2-3)") (class "Default")
      (node (ref "J2") (pin "I/O") (pinfunction "3_I/O") (pintype "bidirectional"))
      (node (ref "R32") (pin "2") (pinfunction "2_2") (pintype "passive"))
    )
    (net (code "45") (name "Net-(J3-2)") (class "Default")
      (node (ref "J3") (pin "PWM") (pinfunction "2_PWM") (pintype "bidirectional"))
      (node (ref "Q4") (pin "2") (pinfunction "D_2") (pintype "passive"))
    )
    (net (code "46") (name "Net-(J3-3)") (class "Default")
      (node (ref "J3") (pin "I/O") (pinfunction "3_I/O") (pintype "bidirectional"))
      (node (ref "R33") (pin "2") (pinfunction "2_2") (pintype "passive"))
    )
    (net (code "47") (name "Net-(J4-2)") (class "Default")
      (node (ref "J4") (pin "PWM") (pinfunction "2_PWM") (pintype "bidirectional"))
      (node (ref "Q5") (pin "2") (pinfunction "D_2") (pintype "passive"))
    )
    (net (code "48") (name "Net-(J4-3)") (class "Default")
      (node (ref "J4") (pin "I/O") (pinfunction "3_I/O") (pintype "bidirectional"))
      (node (ref "R34") (pin "2") (pinfunction "2_2") (pintype "passive"))
    )
    (net (code "49") (name "Net-(J5-2)") (class "Default")
      (node (ref "J5") (pin "PWM") (pinfunction "2_PWM") (pintype "bidirectional"))
      (node (ref "Q6") (pin "2") (pinfunction "D_2") (pintype "passive"))
    )
    (net (code "50") (name "Net-(J5-3)") (class "Default")
      (node (ref "J5") (pin "I/O") (pinfunction "3_I/O") (pintype "bidirectional"))
      (node (ref "R35") (pin "2") (pinfunction "2_2") (pintype "passive"))
    )
    (net (code "51") (name "Net-(LED1-PadA)") (class "Default")
      (node (ref "LED1") (pin "A") (pinfunction "A_A") (pintype "passive"))
      (node (ref "R4") (pin "1") (pinfunction "1_1") (pintype "passive"))
    )
    (net (code "52") (name "Net-(LED4-PadA)") (class "Default")
      (node (ref "LED4") (pin "A") (pinfunction "A_A") (pintype "passive"))
      (node (ref "RL4") (pin "2") (pinfunction "2_2") (pintype "passive"))
    )
    (net (code "53") (name "Net-(LED9-PadA)") (class "Default")
      (node (ref "LED9") (pin "A") (pinfunction "A_A") (pintype "passive"))
      (node (ref "R12") (pin "1") (pinfunction "1_1") (pintype "passive"))
    )
    (net (code "54") (name "Net-(LED10-PadA)") (class "Default")
      (node (ref "LED10") (pin "A") (pinfunction "A_A") (pintype "passive"))
      (node (ref "RL3") (pin "1") (pinfunction "1_1") (pintype "passive"))
    )
    (net (code "55") (name "Net-(LED11-PadA)") (class "Default")
      (node (ref "LED11") (pin "A") (pinfunction "A_A") (pintype "passive"))
      (node (ref "R14") (pin "1") (pinfunction "1_1") (pintype "passive"))
    )
    (net (code "56") (name "Net-(LED11-PadC)") (class "Default")
      (node (ref "LED11") (pin "C") (pinfunction "C_C") (pintype "passive"))
      (node (ref "U$3") (pin "NET") (pinfunction "NET_NET") (pintype "bidirectional"))
    )
    (net (code "57") (name "Net-(LED12-PadA)") (class "Default")
      (node (ref "LED12") (pin "A") (pinfunction "A_A") (pintype "passive"))
      (node (ref "R39") (pin "1") (pinfunction "1_1") (pintype "passive"))
    )
    (net (code "58") (name "Net-(LED12-PadC)") (class "Default")
      (node (ref "LED12") (pin "C") (pinfunction "C_C") (pintype "passive"))
      (node (ref "U$3") (pin "ALM") (pinfunction "ALM_ALM") (pintype "bidirectional"))
    )
    (net (code "59") (name "Net-(LED18-PadA)") (class "Default")
      (node (ref "LED18") (pin "A") (pinfunction "A_A") (pintype "passive"))
      (node (ref "RL1") (pin "2") (pinfunction "2_2") (pintype "passive"))
    )
    (net (code "60") (name "Net-(LED19-PadA)") (class "Default")
      (node (ref "LED19") (pin "A") (pinfunction "A_A") (pintype "passive"))
      (node (ref "RL7") (pin "2") (pinfunction "2_2") (pintype "passive"))
    )
    (net (code "61") (name "Net-(R8-Pad2)") (class "Default")
      (node (ref "R8") (pin "2") (pinfunction "2_2") (pintype "passive"))
      (node (ref "U$3") (pin "TX1") (pinfunction "TX1_TX1") (pintype "bidirectional"))
    )
    (net (code "62") (name "Net-(R11-Pad2)") (class "Default")
      (node (ref "R11") (pin "2") (pinfunction "2_2") (pintype "passive"))
      (node (ref "U$3") (pin "RX1") (pinfunction "RX1_RX1") (pintype "bidirectional"))
    )
    (net (code "63") (name "Net-(R24-Pad2)") (class "Default")
      (node (ref "R24") (pin "2") (pinfunction "2_2") (pintype "passive"))
      (node (ref "X4") (pin "3") (pinfunction "3_3") (pintype "passive"))
    )
    (net (code "64") (name "Net-(R31-Pad2)") (class "Default")
      (node (ref "R31") (pin "2") (pinfunction "2_2") (pintype "passive"))
      (node (ref "X4") (pin "2") (pinfunction "2_2") (pintype "passive"))
    )
    (net (code "65") (name "Net-(RGB-J1-2)") (class "Default")
      (node (ref "Q8") (pin "2") (pinfunction "D_2") (pintype "passive"))
      (node (ref "RGB-J1") (pin "R") (pinfunction "2_R") (pintype "bidirectional"))
    )
    (net (code "66") (name "Net-(RGB-J1-3)") (class "Default")
      (node (ref "Q9") (pin "2") (pinfunction "D_2") (pintype "passive"))
      (node (ref "RGB-J1") (pin "B") (pinfunction "3_B") (pintype "bidirectional"))
    )
    (net (code "67") (name "Net-(RGB-J1-4)") (class "Default")
      (node (ref "Q10") (pin "2") (pinfunction "D_2") (pintype "passive"))
      (node (ref "RGB-J1") (pin "G") (pinfunction "4_G") (pintype "bidirectional"))
    )
    (net (code "68") (name "Net-(RGB-J2-2)") (class "Default")
      (node (ref "Q7") (pin "2") (pinfunction "D_2") (pintype "passive"))
      (node (ref "RGB-J2") (pin "R") (pinfunction "2_R") (pintype "bidirectional"))
    )
    (net (code "69") (name "Net-(RGB-J2-3)") (class "Default")
      (node (ref "Q11") (pin "2") (pinfunction "D_2") (pintype "passive"))
      (node (ref "RGB-J2") (pin "B") (pinfunction "3_B") (pintype "bidirectional"))
    )
    (net (code "70") (name "Net-(RGB-J2-4)") (class "Default")
      (node (ref "Q12") (pin "2") (pinfunction "D_2") (pintype "passive"))
      (node (ref "RGB-J2") (pin "G") (pinfunction "4_G") (pintype "bidirectional"))
    )
    (net (code "71") (name "Net-(U$1-DACL)") (class "Default")
      (node (ref "U$1") (pin "5") (pinfunction "DACL_5") (pintype "output"))
      (node (ref "X1") (pin "2") (pinfunction "2_2") (pintype "passive"))
    )
    (net (code "72") (name "Net-(U$1-DACR)") (class "Default")
      (node (ref "U$1") (pin "4") (pinfunction "DACR_4") (pintype "output"))
      (node (ref "X1") (pin "3") (pinfunction "3_3") (pintype "passive"))
    )
    (net (code "73") (name "Net-(U$1-RX)") (class "Default")
      (node (ref "R1") (pin "1") (pinfunction "1_1") (pintype "passive"))
      (node (ref "U$1") (pin "2") (pinfunction "RX_2") (pintype "input"))
    )
    (net (code "74") (name "Net-(U$1-TX)") (class "Default")
      (node (ref "R2") (pin "1") (pinfunction "1_1") (pintype "passive"))
      (node (ref "U$1") (pin "3") (pinfunction "TX_3") (pintype "output"))
    )
    (net (code "75") (name "Net-(U$3-RNU)") (class "Default")
      (node (ref "LED9") (pin "C") (pinfunction "C_C") (pintype "passive"))
      (node (ref "U$3") (pin "RUN") (pinfunction "RNU_RUN") (pintype "bidirectional"))
    )
    (net (code "76") (name "Net-(U$4-UCAP)") (class "Default")
      (node (ref "C3") (pin "2") (pinfunction "2_2") (pintype "passive"))
      (node (ref "U$4") (pin "6") (pinfunction "UCAP_6") (pintype "bidirectional"))
    )
    (net (code "77") (name "VUSB") (class "Default")
      (node (ref "C7") (pin "2") (pinfunction "2_2") (pintype "passive"))
      (node (ref "D4") (pin "A") (pinfunction "A_A") (pintype "passive"))
      (node (ref "U$4") (pin "7") (pinfunction "VBUS_7") (pintype "bidirectional"))
      (node (ref "X4") (pin "1") (pinfunction "1_1") (pintype "passive"))
    )
    (net (code "78") (name "unconnected-(CFG-Pad2)") (class "Default")
      (node (ref "CFG") (pin "2") (pinfunction "2_2") (pintype "passive"))
    )
    (net (code "79") (name "unconnected-(CFG-Pad3)") (class "Default")
      (node (ref "CFG") (pin "3") (pinfunction "3_3") (pintype "passive"))
    )
    (net (code "80") (name "unconnected-(Q1-D-Pad4)") (class "Default")
      (node (ref "Q1") (pin "4") (pinfunction "D_4") (pintype "passive"))
    )
    (net (code "81") (name "unconnected-(Q2-D-Pad4)") (class "Default")
      (node (ref "Q2") (pin "4") (pinfunction "D_4") (pintype "passive"))
    )
    (net (code "82") (name "unconnected-(Q4-D-Pad4)") (class "Default")
      (node (ref "Q4") (pin "4") (pinfunction "D_4") (pintype "passive"))
    )
    (net (code "83") (name "unconnected-(Q5-D-Pad4)") (class "Default")
      (node (ref "Q5") (pin "4") (pinfunction "D_4") (pintype "passive"))
    )
    (net (code "84") (name "unconnected-(Q6-D-Pad4)") (class "Default")
      (node (ref "Q6") (pin "4") (pinfunction "D_4") (pintype "passive"))
    )
    (net (code "85") (name "unconnected-(Q7-D-Pad4)") (class "Default")
      (node (ref "Q7") (pin "4") (pinfunction "D_4") (pintype "passive"))
    )
    (net (code "86") (name "unconnected-(Q8-D-Pad4)") (class "Default")
      (node (ref "Q8") (pin "4") (pinfunction "D_4") (pintype "passive"))
    )
    (net (code "87") (name "unconnected-(Q9-D-Pad4)") (class "Default")
      (node (ref "Q9") (pin "4") (pinfunction "D_4") (pintype "passive"))
    )
    (net (code "88") (name "unconnected-(Q10-D-Pad4)") (class "Default")
      (node (ref "Q10") (pin "4") (pinfunction "D_4") (pintype "passive"))
    )
    (net (code "89") (name "unconnected-(Q11-D-Pad4)") (class "Default")
      (node (ref "Q11") (pin "4") (pinfunction "D_4") (pintype "passive"))
    )
    (net (code "90") (name "unconnected-(Q12-D-Pad4)") (class "Default")
      (node (ref "Q12") (pin "4") (pinfunction "D_4") (pintype "passive"))
    )
    (net (code "91") (name "unconnected-(RESET1-Pad1)") (class "Default")
      (node (ref "RESET1") (pin "1") (pinfunction "1_1") (pintype "passive"))
    )
    (net (code "92") (name "unconnected-(RESET1-Pad3)") (class "Default")
      (node (ref "RESET1") (pin "3") (pinfunction "3_3") (pintype "passive"))
    )
    (net (code "93") (name "unconnected-(U$1-BUSY-Pad16)") (class "Default")
      (node (ref "U$1") (pin "16") (pinfunction "BUSY_16") (pintype "output"))
    )
    (net (code "94") (name "unconnected-(U$1-IO1-Pad9)") (class "Default")
      (node (ref "U$1") (pin "9") (pinfunction "IO1_9") (pintype "bidirectional"))
    )
    (net (code "95") (name "unconnected-(U$1-IO2-Pad11)") (class "Default")
      (node (ref "U$1") (pin "11") (pinfunction "IO2_11") (pintype "bidirectional"))
    )
    (net (code "96") (name "unconnected-(U$1-KEY1-Pad12)") (class "Default")
      (node (ref "U$1") (pin "12") (pinfunction "KEY1_12") (pintype "input"))
    )
    (net (code "97") (name "unconnected-(U$1-KEY2-Pad13)") (class "Default")
      (node (ref "U$1") (pin "13") (pinfunction "KEY2_13") (pintype "input"))
    )
    (net (code "98") (name "unconnected-(U$1-SPK1-Pad6)") (class "Default")
      (node (ref "U$1") (pin "6") (pinfunction "SPK1_6") (pintype "output"))
    )
    (net (code "99") (name "unconnected-(U$1-SPK2-Pad8)") (class "Default")
      (node (ref "U$1") (pin "8") (pinfunction "SPK2_8") (pintype "output"))
    )
    (net (code "100") (name "unconnected-(U$1-USB+-Pad14)") (class "Default")
      (node (ref "U$1") (pin "14") (pinfunction "USB+_14") (pintype "bidirectional"))
    )
    (net (code "101") (name "unconnected-(U$1-USB--Pad15)") (class "Default")
      (node (ref "U$1") (pin "15") (pinfunction "USB-_15") (pintype "bidirectional"))
    )
    (net (code "102") (name "unconnected-(U$3-PadRST)") (class "Default")
      (node (ref "U$3") (pin "RST") (pinfunction "RST_RST") (pintype "bidirectional"))
    )
    (net (code "103") (name "unconnected-(X1-Pad4)") (class "Default")
      (node (ref "X1") (pin "4") (pinfunction "4_4") (pintype "passive"))
    )
    (net (code "104") (name "unconnected-(X1-Pad5)") (class "Default")
      (node (ref "X1") (pin "5") (pinfunction "5_5") (pintype "passive"))
    )
    (net (code "105") (name "unconnected-(X4-Pad4)") (class "Default")
      (node (ref "X4") (pin "4") (pinfunction "4_4") (pintype "passive"))
    )
  )
)
